# LED_Board.net
KiCad netlist of a schematic drawn in EAGLE
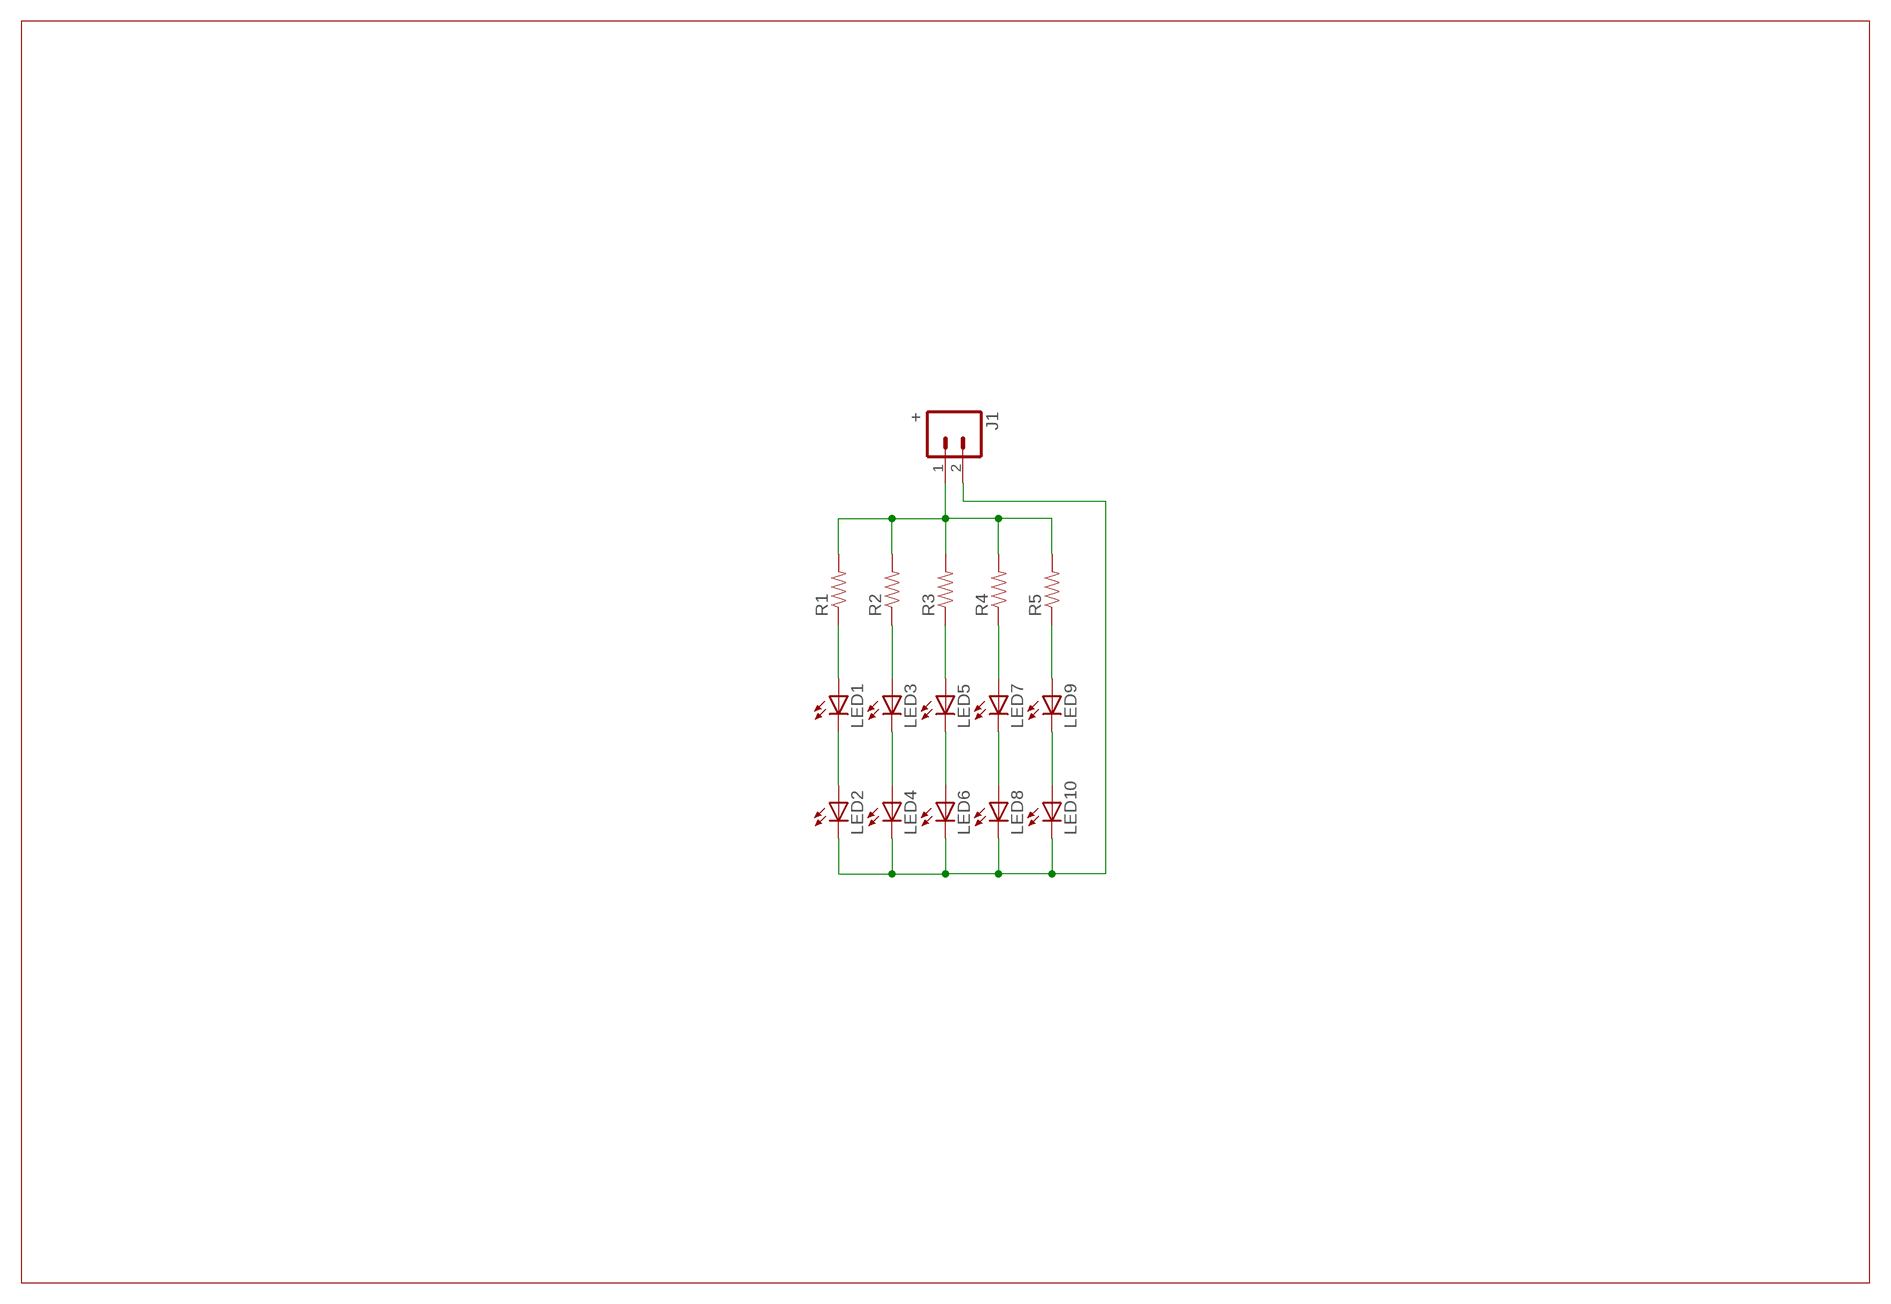
[diagram p0: schematic, sheet 1]

(export (version "E")
  (design (tool "Eeschema 10.0.6"))
  (components
    (comp (ref "J1")
      (value "+")
      (footprint "eagle-import:1X02_LOCK")
      (libsource (lib "eagle-import") (part "M02LOCK"))
    )
    (comp (ref "LED1")
      (value "LED5MM")
      (footprint "eagle-import:LED5MM")
      (libsource (lib "eagle-import") (part "LED5MM"))
    )
    (comp (ref "LED2")
      (value "LED5MM")
      (footprint "eagle-import:LED5MM")
      (libsource (lib "eagle-import") (part "LED5MM"))
    )
    (comp (ref "LED3")
      (value "LED5MM")
      (footprint "eagle-import:LED5MM")
      (libsource (lib "eagle-import") (part "LED5MM"))
    )
    (comp (ref "LED4")
      (value "LED5MM")
      (footprint "eagle-import:LED5MM")
      (libsource (lib "eagle-import") (part "LED5MM"))
    )
    (comp (ref "LED5")
      (value "LED5MM")
      (footprint "eagle-import:LED5MM")
      (libsource (lib "eagle-import") (part "LED5MM"))
    )
    (comp (ref "LED6")
      (value "LED5MM")
      (footprint "eagle-import:LED5MM")
      (libsource (lib "eagle-import") (part "LED5MM"))
    )
    (comp (ref "LED7")
      (value "LED5MM")
      (footprint "eagle-import:LED5MM")
      (libsource (lib "eagle-import") (part "LED5MM"))
    )
    (comp (ref "LED8")
      (value "LED5MM")
      (footprint "eagle-import:LED5MM")
      (libsource (lib "eagle-import") (part "LED5MM"))
    )
    (comp (ref "LED9")
      (value "LED5MM")
      (footprint "eagle-import:LED5MM")
      (libsource (lib "eagle-import") (part "LED5MM"))
    )
    (comp (ref "LED10")
      (value "LED5MM")
      (footprint "eagle-import:LED5MM")
      (libsource (lib "eagle-import") (part "LED5MM"))
    )
    (comp (ref "R1")
      (value "RESISTOR1206")
      (footprint "eagle-import:1206")
      (libsource (lib "eagle-import") (part "RESISTOR1206"))
    )
    (comp (ref "R2")
      (value "RESISTOR1206")
      (footprint "eagle-import:1206")
      (libsource (lib "eagle-import") (part "RESISTOR1206"))
    )
    (comp (ref "R3")
      (value "RESISTOR1206")
      (footprint "eagle-import:1206")
      (libsource (lib "eagle-import") (part "RESISTOR1206"))
    )
    (comp (ref "R4")
      (value "RESISTOR1206")
      (footprint "eagle-import:1206")
      (libsource (lib "eagle-import") (part "RESISTOR1206"))
    )
    (comp (ref "R5")
      (value "RESISTOR1206")
      (footprint "eagle-import:1206")
      (libsource (lib "eagle-import") (part "RESISTOR1206"))
    )
  )
  (nets
    (net (code "1") (name "Net-(J1-Pad1)") (class "Default")
      (node (ref "J1") (pin "1") (pinfunction "1_1") (pintype "passive"))
      (node (ref "R1") (pin "2") (pinfunction "2_2") (pintype "passive"))
      (node (ref "R2") (pin "2") (pinfunction "2_2") (pintype "passive"))
      (node (ref "R3") (pin "2") (pinfunction "2_2") (pintype "passive"))
      (node (ref "R4") (pin "2") (pinfunction "2_2") (pintype "passive"))
      (node (ref "R5") (pin "2") (pinfunction "2_2") (pintype "passive"))
    )
    (net (code "2") (name "Net-(LED1-C)") (class "Default")
      (node (ref "LED1") (pin "K") (pinfunction "C_K") (pintype "passive"))
      (node (ref "LED2") (pin "A") (pinfunction "A_A") (pintype "passive"))
    )
    (net (code "3") (name "Net-(LED1-PadA)") (class "Default")
      (node (ref "LED1") (pin "A") (pinfunction "A_A") (pintype "passive"))
      (node (ref "R1") (pin "1") (pinfunction "1_1") (pintype "passive"))
    )
    (net (code "4") (name "Net-(LED3-C)") (class "Default")
      (node (ref "LED3") (pin "K") (pinfunction "C_K") (pintype "passive"))
      (node (ref "LED4") (pin "A") (pinfunction "A_A") (pintype "passive"))
    )
    (net (code "5") (name "Net-(LED3-PadA)") (class "Default")
      (node (ref "LED3") (pin "A") (pinfunction "A_A") (pintype "passive"))
      (node (ref "R2") (pin "1") (pinfunction "1_1") (pintype "passive"))
    )
    (net (code "6") (name "Net-(LED5-C)") (class "Default")
      (node (ref "LED5") (pin "K") (pinfunction "C_K") (pintype "passive"))
      (node (ref "LED6") (pin "A") (pinfunction "A_A") (pintype "passive"))
    )
    (net (code "7") (name "Net-(LED5-PadA)") (class "Default")
      (node (ref "LED5") (pin "A") (pinfunction "A_A") (pintype "passive"))
      (node (ref "R3") (pin "1") (pinfunction "1_1") (pintype "passive"))
    )
    (net (code "8") (name "Net-(LED7-C)") (class "Default")
      (node (ref "LED7") (pin "K") (pinfunction "C_K") (pintype "passive"))
      (node (ref "LED8") (pin "A") (pinfunction "A_A") (pintype "passive"))
    )
    (net (code "9") (name "Net-(LED7-PadA)") (class "Default")
      (node (ref "LED7") (pin "A") (pinfunction "A_A") (pintype "passive"))
      (node (ref "R4") (pin "1") (pinfunction "1_1") (pintype "passive"))
    )
    (net (code "10") (name "Net-(LED9-C)") (class "Default")
      (node (ref "LED10") (pin "A") (pinfunction "A_A") (pintype "passive"))
      (node (ref "LED9") (pin "K") (pinfunction "C_K") (pintype "passive"))
    )
    (net (code "11") (name "Net-(LED9-PadA)") (class "Default")
      (node (ref "LED9") (pin "A") (pinfunction "A_A") (pintype "passive"))
      (node (ref "R5") (pin "1") (pinfunction "1_1") (pintype "passive"))
    )
    (net (code "12") (name "Net-(LED10-C)") (class "Default")
      (node (ref "J1") (pin "2") (pinfunction "2_2") (pintype "passive"))
      (node (ref "LED10") (pin "K") (pinfunction "C_K") (pintype "passive"))
      (node (ref "LED2") (pin "K") (pinfunction "C_K") (pintype "passive"))
      (node (ref "LED4") (pin "K") (pinfunction "C_K") (pintype "passive"))
      (node (ref "LED6") (pin "K") (pinfunction "C_K") (pintype "passive"))
      (node (ref "LED8") (pin "K") (pinfunction "C_K") (pintype "passive"))
    )
  )
)
